# Pure_Seq_SMD_V2_2.net
KiCad netlist of a schematic drawn in EAGLE
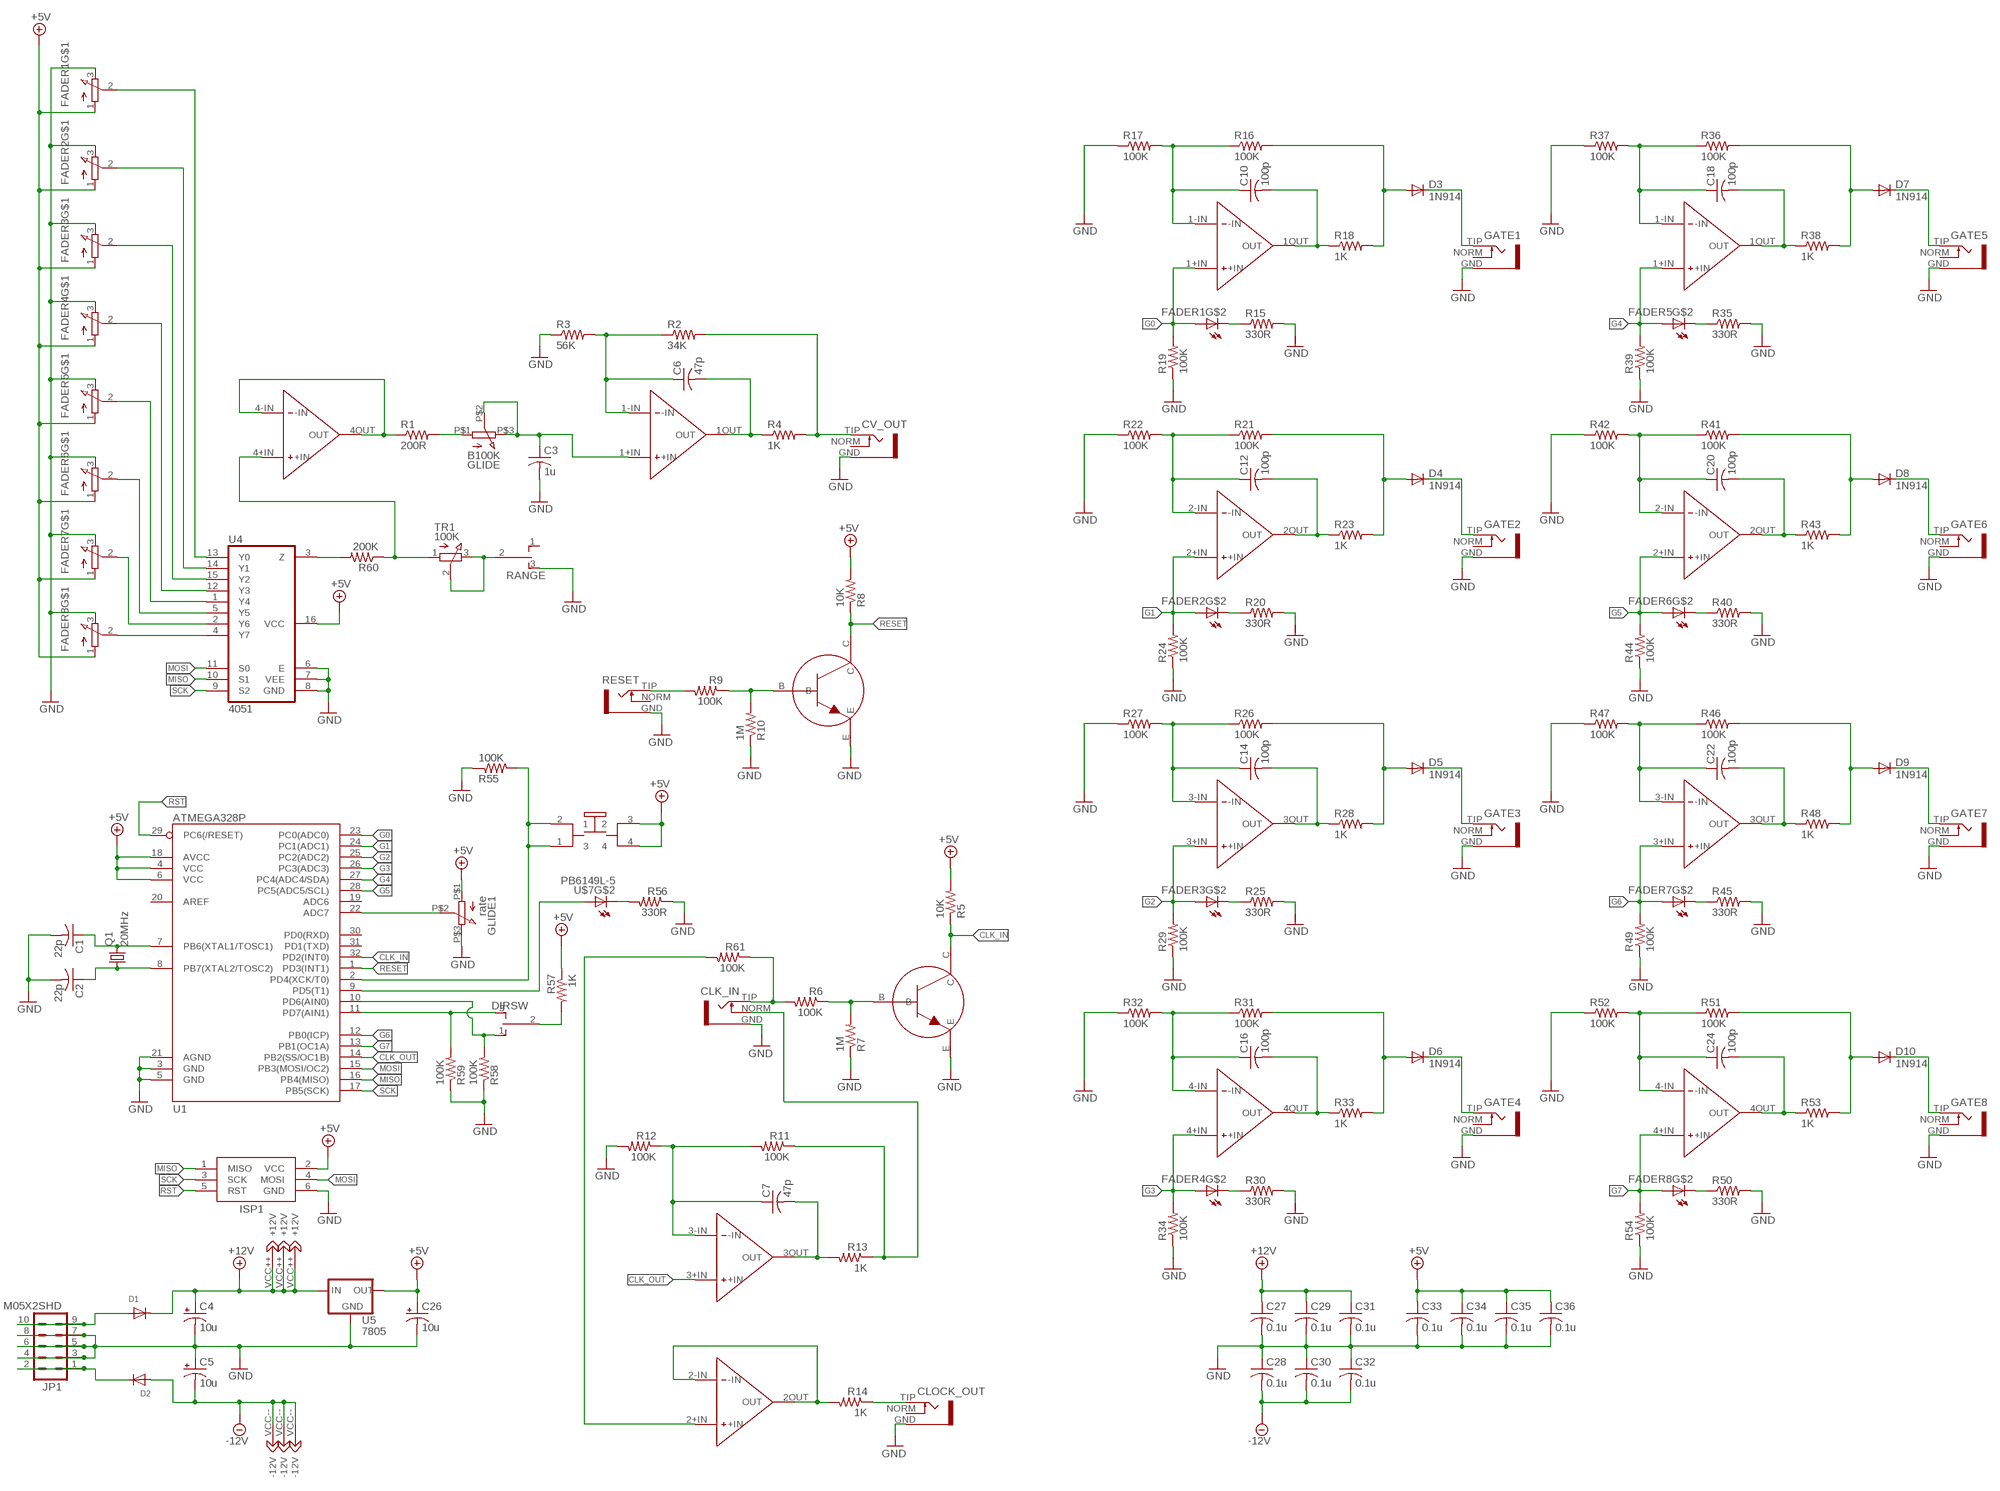
[diagram p0: schematic, sheet 1]

(export (version "E")
  (design (tool "Eeschema 10.0.6"))
  (components
    (comp (ref "C1")
      (value "22p")
      (footprint "eagle-import:C0805K")
      (libsource (lib "eagle-import") (part "C-USC0805K"))
    )
    (comp (ref "C2")
      (value "22p")
      (footprint "eagle-import:C0805K")
      (libsource (lib "eagle-import") (part "C-USC0805K"))
    )
    (comp (ref "C3")
      (value "1u")
      (footprint "eagle-import:C0805K")
      (libsource (lib "eagle-import") (part "C-USC0805K"))
    )
    (comp (ref "C4")
      (value "10u")
      (footprint "eagle-import:153CLV-0505")
      (libsource (lib "eagle-import") (part "CPOL-US153CLV-0505"))
    )
    (comp (ref "C5")
      (value "10u")
      (footprint "eagle-import:153CLV-0505")
      (libsource (lib "eagle-import") (part "CPOL-US153CLV-0505"))
    )
    (comp (ref "C6")
      (value "47p")
      (footprint "eagle-import:C0805K")
      (libsource (lib "eagle-import") (part "C-USC0805K"))
    )
    (comp (ref "C7")
      (value "47p")
      (footprint "eagle-import:C0805K")
      (libsource (lib "eagle-import") (part "C-USC0805K"))
    )
    (comp (ref "C10")
      (value "100p")
      (footprint "eagle-import:C0805K")
      (libsource (lib "eagle-import") (part "C-USC0805K"))
    )
    (comp (ref "C12")
      (value "100p")
      (footprint "eagle-import:C0805K")
      (libsource (lib "eagle-import") (part "C-USC0805K"))
    )
    (comp (ref "C14")
      (value "100p")
      (footprint "eagle-import:C0805K")
      (libsource (lib "eagle-import") (part "C-USC0805K"))
    )
    (comp (ref "C16")
      (value "100p")
      (footprint "eagle-import:C0805K")
      (libsource (lib "eagle-import") (part "C-USC0805K"))
    )
    (comp (ref "C18")
      (value "100p")
      (footprint "eagle-import:C0805K")
      (libsource (lib "eagle-import") (part "C-USC0805K"))
    )
    (comp (ref "C20")
      (value "100p")
      (footprint "eagle-import:C0805K")
      (libsource (lib "eagle-import") (part "C-USC0805K"))
    )
    (comp (ref "C22")
      (value "100p")
      (footprint "eagle-import:C0805K")
      (libsource (lib "eagle-import") (part "C-USC0805K"))
    )
    (comp (ref "C24")
      (value "100p")
      (footprint "eagle-import:C0805K")
      (libsource (lib "eagle-import") (part "C-USC0805K"))
    )
    (comp (ref "C26")
      (value "10u")
      (footprint "eagle-import:153CLV-0505")
      (libsource (lib "eagle-import") (part "CPOL-US153CLV-0505"))
    )
    (comp (ref "C27")
      (value "0.1u")
      (footprint "eagle-import:C0805K")
      (libsource (lib "eagle-import") (part "C-USC0805K"))
    )
    (comp (ref "C28")
      (value "0.1u")
      (footprint "eagle-import:C0805K")
      (libsource (lib "eagle-import") (part "C-USC0805K"))
    )
    (comp (ref "C29")
      (value "0.1u")
      (footprint "eagle-import:C0805K")
      (libsource (lib "eagle-import") (part "C-USC0805K"))
    )
    (comp (ref "C30")
      (value "0.1u")
      (footprint "eagle-import:C0805K")
      (libsource (lib "eagle-import") (part "C-USC0805K"))
    )
    (comp (ref "C31")
      (value "0.1u")
      (footprint "eagle-import:C0805K")
      (libsource (lib "eagle-import") (part "C-USC0805K"))
    )
    (comp (ref "C32")
      (value "0.1u")
      (footprint "eagle-import:C0805K")
      (libsource (lib "eagle-import") (part "C-USC0805K"))
    )
    (comp (ref "C33")
      (value "0.1u")
      (footprint "eagle-import:C0805K")
      (libsource (lib "eagle-import") (part "C-USC0805K"))
    )
    (comp (ref "C34")
      (value "0.1u")
      (footprint "eagle-import:C0805K")
      (libsource (lib "eagle-import") (part "C-USC0805K"))
    )
    (comp (ref "C35")
      (value "0.1u")
      (footprint "eagle-import:C0805K")
      (libsource (lib "eagle-import") (part "C-USC0805K"))
    )
    (comp (ref "C36")
      (value "0.1u")
      (footprint "eagle-import:C0805K")
      (libsource (lib "eagle-import") (part "C-USC0805K"))
    )
    (comp (ref "CLK_IN")
      (value "S_JACK")
      (footprint "eagle-import:S_JACK")
      (libsource (lib "eagle-import") (part "S_JACK"))
    )
    (comp (ref "CLOCK_OUT")
      (value "S_JACK")
      (footprint "eagle-import:S_JACK")
      (libsource (lib "eagle-import") (part "S_JACK"))
    )
    (comp (ref "CV_OUT")
      (value "S_JACK")
      (footprint "eagle-import:S_JACK")
      (libsource (lib "eagle-import") (part "S_JACK"))
    )
    (comp (ref "D1")
      (value "DIODESMA")
      (footprint "eagle-import:SMADIODE")
      (libsource (lib "eagle-import") (part "adafruit_DIODESMA"))
    )
    (comp (ref "D2")
      (value "DIODESMA")
      (footprint "eagle-import:SMADIODE")
      (libsource (lib "eagle-import") (part "adafruit_DIODESMA"))
    )
    (comp (ref "D3")
      (value "1N914")
      (footprint "eagle-import:SOD-323")
      (libsource (lib "eagle-import") (part "DIODESOD"))
    )
    (comp (ref "D4")
      (value "1N914")
      (footprint "eagle-import:SOD-323")
      (libsource (lib "eagle-import") (part "DIODESOD"))
    )
    (comp (ref "D5")
      (value "1N914")
      (footprint "eagle-import:SOD-323")
      (libsource (lib "eagle-import") (part "DIODESOD"))
    )
    (comp (ref "D6")
      (value "1N914")
      (footprint "eagle-import:SOD-323")
      (libsource (lib "eagle-import") (part "DIODESOD"))
    )
    (comp (ref "D7")
      (value "1N914")
      (footprint "eagle-import:SOD-323")
      (libsource (lib "eagle-import") (part "DIODESOD"))
    )
    (comp (ref "D8")
      (value "1N914")
      (footprint "eagle-import:SOD-323")
      (libsource (lib "eagle-import") (part "DIODESOD"))
    )
    (comp (ref "D9")
      (value "1N914")
      (footprint "eagle-import:SOD-323")
      (libsource (lib "eagle-import") (part "DIODESOD"))
    )
    (comp (ref "D10")
      (value "1N914")
      (footprint "eagle-import:SOD-323")
      (libsource (lib "eagle-import") (part "DIODESOD"))
    )
    (comp (ref "DIRSW")
      (value "TOGGLE_ON_OFF_ON")
      (footprint "eagle-import:TOGGLE_ON_OFF_ON")
      (libsource (lib "eagle-import") (part "TOGGLE_ON_OFF_ON"))
    )
    (comp (ref "FADER1")
      (value "LED_FADER")
      (footprint "eagle-import:LED_FADER")
      (libsource (lib "eagle-import") (part "LED_FADER"))
    )
    (comp (ref "FADER2")
      (value "LED_FADER")
      (footprint "eagle-import:LED_FADER")
      (libsource (lib "eagle-import") (part "LED_FADER"))
    )
    (comp (ref "FADER3")
      (value "LED_FADER")
      (footprint "eagle-import:LED_FADER")
      (libsource (lib "eagle-import") (part "LED_FADER"))
    )
    (comp (ref "FADER4")
      (value "LED_FADER")
      (footprint "eagle-import:LED_FADER")
      (libsource (lib "eagle-import") (part "LED_FADER"))
    )
    (comp (ref "FADER5")
      (value "LED_FADER")
      (footprint "eagle-import:LED_FADER")
      (libsource (lib "eagle-import") (part "LED_FADER"))
    )
    (comp (ref "FADER6")
      (value "LED_FADER")
      (footprint "eagle-import:LED_FADER")
      (libsource (lib "eagle-import") (part "LED_FADER"))
    )
    (comp (ref "FADER7")
      (value "LED_FADER")
      (footprint "eagle-import:LED_FADER")
      (libsource (lib "eagle-import") (part "LED_FADER"))
    )
    (comp (ref "FADER8")
      (value "LED_FADER")
      (footprint "eagle-import:LED_FADER")
      (libsource (lib "eagle-import") (part "LED_FADER"))
    )
    (comp (ref "GATE1")
      (value "S_JACK")
      (footprint "eagle-import:S_JACK")
      (libsource (lib "eagle-import") (part "S_JACK"))
    )
    (comp (ref "GATE2")
      (value "S_JACK")
      (footprint "eagle-import:S_JACK")
      (libsource (lib "eagle-import") (part "S_JACK"))
    )
    (comp (ref "GATE3")
      (value "S_JACK")
      (footprint "eagle-import:S_JACK")
      (libsource (lib "eagle-import") (part "S_JACK"))
    )
    (comp (ref "GATE4")
      (value "S_JACK")
      (footprint "eagle-import:S_JACK")
      (libsource (lib "eagle-import") (part "S_JACK"))
    )
    (comp (ref "GATE5")
      (value "S_JACK")
      (footprint "eagle-import:S_JACK")
      (libsource (lib "eagle-import") (part "S_JACK"))
    )
    (comp (ref "GATE6")
      (value "S_JACK")
      (footprint "eagle-import:S_JACK")
      (libsource (lib "eagle-import") (part "S_JACK"))
    )
    (comp (ref "GATE7")
      (value "S_JACK")
      (footprint "eagle-import:S_JACK")
      (libsource (lib "eagle-import") (part "S_JACK"))
    )
    (comp (ref "GATE8")
      (value "S_JACK")
      (footprint "eagle-import:S_JACK")
      (libsource (lib "eagle-import") (part "S_JACK"))
    )
    (comp (ref "GLIDE")
      (value "B100K")
      (footprint "eagle-import:Q-POT")
      (libsource (lib "eagle-import") (part "Q-POT"))
    )
    (comp (ref "GLIDE1")
      (value "rate")
      (footprint "eagle-import:Q-POT")
      (libsource (lib "eagle-import") (part "Q-POT"))
    )
    (comp (ref "ISP1")
      (value "AVRISP-6")
      (footprint "eagle-import:AVRISP")
      (libsource (lib "eagle-import") (part "AVRISP-6"))
    )
    (comp (ref "JP1")
      (value "M05X2SHD")
      (footprint "eagle-import:2X5-SHROUDED")
      (libsource (lib "eagle-import") (part "M05X2SHD"))
    )
    (comp (ref "Q1")
      (value "20MHz")
      (footprint "eagle-import:HC49UP")
      (libsource (lib "eagle-import") (part "CRYSTALHC49UP"))
    )
    (comp (ref "R1")
      (value "200R")
      (footprint "eagle-import:R0805")
      (libsource (lib "eagle-import") (part "R-US_R0805"))
    )
    (comp (ref "R2")
      (value "34K")
      (footprint "eagle-import:R0805")
      (libsource (lib "eagle-import") (part "R-US_R0805"))
    )
    (comp (ref "R3")
      (value "56K")
      (footprint "eagle-import:R0805")
      (libsource (lib "eagle-import") (part "R-US_R0805"))
    )
    (comp (ref "R4")
      (value "1K")
      (footprint "eagle-import:R0805")
      (libsource (lib "eagle-import") (part "R-US_R0805"))
    )
    (comp (ref "R5")
      (value "10K")
      (footprint "eagle-import:R0805")
      (libsource (lib "eagle-import") (part "R-US_R0805"))
    )
    (comp (ref "R6")
      (value "100K")
      (footprint "eagle-import:R0805")
      (libsource (lib "eagle-import") (part "R-US_R0805"))
    )
    (comp (ref "R7")
      (value "1M")
      (footprint "eagle-import:R0805")
      (libsource (lib "eagle-import") (part "R-US_R0805"))
    )
    (comp (ref "R8")
      (value "10K")
      (footprint "eagle-import:R0805")
      (libsource (lib "eagle-import") (part "R-US_R0805"))
    )
    (comp (ref "R9")
      (value "100K")
      (footprint "eagle-import:R0805")
      (libsource (lib "eagle-import") (part "R-US_R0805"))
    )
    (comp (ref "R10")
      (value "1M")
      (footprint "eagle-import:R0805")
      (libsource (lib "eagle-import") (part "R-US_R0805"))
    )
    (comp (ref "R11")
      (value "100K")
      (footprint "eagle-import:R0805")
      (libsource (lib "eagle-import") (part "R-US_R0805"))
    )
    (comp (ref "R12")
      (value "100K")
      (footprint "eagle-import:R0805")
      (libsource (lib "eagle-import") (part "R-US_R0805"))
    )
    (comp (ref "R13")
      (value "1K")
      (footprint "eagle-import:R0805")
      (libsource (lib "eagle-import") (part "R-US_R0805"))
    )
    (comp (ref "R14")
      (value "1K")
      (footprint "eagle-import:R0805")
      (libsource (lib "eagle-import") (part "R-US_R0805"))
    )
    (comp (ref "R15")
      (value "330R")
      (footprint "eagle-import:R0805")
      (libsource (lib "eagle-import") (part "R-US_R0805"))
    )
    (comp (ref "R16")
      (value "100K")
      (footprint "eagle-import:R0805")
      (libsource (lib "eagle-import") (part "R-US_R0805"))
    )
    (comp (ref "R17")
      (value "100K")
      (footprint "eagle-import:R0805")
      (libsource (lib "eagle-import") (part "R-US_R0805"))
    )
    (comp (ref "R18")
      (value "1K")
      (footprint "eagle-import:R0805")
      (libsource (lib "eagle-import") (part "R-US_R0805"))
    )
    (comp (ref "R19")
      (value "100K")
      (footprint "eagle-import:R0805")
      (libsource (lib "eagle-import") (part "R-US_R0805"))
    )
    (comp (ref "R20")
      (value "330R")
      (footprint "eagle-import:R0805")
      (libsource (lib "eagle-import") (part "R-US_R0805"))
    )
    (comp (ref "R21")
      (value "100K")
      (footprint "eagle-import:R0805")
      (libsource (lib "eagle-import") (part "R-US_R0805"))
    )
    (comp (ref "R22")
      (value "100K")
      (footprint "eagle-import:R0805")
      (libsource (lib "eagle-import") (part "R-US_R0805"))
    )
    (comp (ref "R23")
      (value "1K")
      (footprint "eagle-import:R0805")
      (libsource (lib "eagle-import") (part "R-US_R0805"))
    )
    (comp (ref "R24")
      (value "100K")
      (footprint "eagle-import:R0805")
      (libsource (lib "eagle-import") (part "R-US_R0805"))
    )
    (comp (ref "R25")
      (value "330R")
      (footprint "eagle-import:R0805")
      (libsource (lib "eagle-import") (part "R-US_R0805"))
    )
    (comp (ref "R26")
      (value "100K")
      (footprint "eagle-import:R0805")
      (libsource (lib "eagle-import") (part "R-US_R0805"))
    )
    (comp (ref "R27")
      (value "100K")
      (footprint "eagle-import:R0805")
      (libsource (lib "eagle-import") (part "R-US_R0805"))
    )
    (comp (ref "R28")
      (value "1K")
      (footprint "eagle-import:R0805")
      (libsource (lib "eagle-import") (part "R-US_R0805"))
    )
    (comp (ref "R29")
      (value "100K")
      (footprint "eagle-import:R0805")
      (libsource (lib "eagle-import") (part "R-US_R0805"))
    )
    (comp (ref "R30")
      (value "330R")
      (footprint "eagle-import:R0805")
      (libsource (lib "eagle-import") (part "R-US_R0805"))
    )
    (comp (ref "R31")
      (value "100K")
      (footprint "eagle-import:R0805")
      (libsource (lib "eagle-import") (part "R-US_R0805"))
    )
    (comp (ref "R32")
      (value "100K")
      (footprint "eagle-import:R0805")
      (libsource (lib "eagle-import") (part "R-US_R0805"))
    )
    (comp (ref "R33")
      (value "1K")
      (footprint "eagle-import:R0805")
      (libsource (lib "eagle-import") (part "R-US_R0805"))
    )
    (comp (ref "R34")
      (value "100K")
      (footprint "eagle-import:R0805")
      (libsource (lib "eagle-import") (part "R-US_R0805"))
    )
    (comp (ref "R35")
      (value "330R")
      (footprint "eagle-import:R0805")
      (libsource (lib "eagle-import") (part "R-US_R0805"))
    )
    (comp (ref "R36")
      (value "100K")
      (footprint "eagle-import:R0805")
      (libsource (lib "eagle-import") (part "R-US_R0805"))
    )
    (comp (ref "R37")
      (value "100K")
      (footprint "eagle-import:R0805")
      (libsource (lib "eagle-import") (part "R-US_R0805"))
    )
    (comp (ref "R38")
      (value "1K")
      (footprint "eagle-import:R0805")
      (libsource (lib "eagle-import") (part "R-US_R0805"))
    )
    (comp (ref "R39")
      (value "100K")
      (footprint "eagle-import:R0805")
      (libsource (lib "eagle-import") (part "R-US_R0805"))
    )
    (comp (ref "R40")
      (value "330R")
      (footprint "eagle-import:R0805")
      (libsource (lib "eagle-import") (part "R-US_R0805"))
    )
    (comp (ref "R41")
      (value "100K")
      (footprint "eagle-import:R0805")
      (libsource (lib "eagle-import") (part "R-US_R0805"))
    )
    (comp (ref "R42")
      (value "100K")
      (footprint "eagle-import:R0805")
      (libsource (lib "eagle-import") (part "R-US_R0805"))
    )
    (comp (ref "R43")
      (value "1K")
      (footprint "eagle-import:R0805")
      (libsource (lib "eagle-import") (part "R-US_R0805"))
    )
    (comp (ref "R44")
      (value "100K")
      (footprint "eagle-import:R0805")
      (libsource (lib "eagle-import") (part "R-US_R0805"))
    )
    (comp (ref "R45")
      (value "330R")
      (footprint "eagle-import:R0805")
      (libsource (lib "eagle-import") (part "R-US_R0805"))
    )
    (comp (ref "R46")
      (value "100K")
      (footprint "eagle-import:R0805")
      (libsource (lib "eagle-import") (part "R-US_R0805"))
    )
    (comp (ref "R47")
      (value "100K")
      (footprint "eagle-import:R0805")
      (libsource (lib "eagle-import") (part "R-US_R0805"))
    )
    (comp (ref "R48")
      (value "1K")
      (footprint "eagle-import:R0805")
      (libsource (lib "eagle-import") (part "R-US_R0805"))
    )
    (comp (ref "R49")
      (value "100K")
      (footprint "eagle-import:R0805")
      (libsource (lib "eagle-import") (part "R-US_R0805"))
    )
    (comp (ref "R50")
      (value "330R")
      (footprint "eagle-import:R0805")
      (libsource (lib "eagle-import") (part "R-US_R0805"))
    )
    (comp (ref "R51")
      (value "100K")
      (footprint "eagle-import:R0805")
      (libsource (lib "eagle-import") (part "R-US_R0805"))
    )
    (comp (ref "R52")
      (value "100K")
      (footprint "eagle-import:R0805")
      (libsource (lib "eagle-import") (part "R-US_R0805"))
    )
    (comp (ref "R53")
      (value "1K")
      (footprint "eagle-import:R0805")
      (libsource (lib "eagle-import") (part "R-US_R0805"))
    )
    (comp (ref "R54")
      (value "100K")
      (footprint "eagle-import:R0805")
      (libsource (lib "eagle-import") (part "R-US_R0805"))
    )
    (comp (ref "R55")
      (value "100K")
      (footprint "eagle-import:R0805")
      (libsource (lib "eagle-import") (part "R-US_R0805"))
    )
    (comp (ref "R56")
      (value "330R")
      (footprint "eagle-import:R0805")
      (libsource (lib "eagle-import") (part "R-US_R0805"))
    )
    (comp (ref "R57")
      (value "1K")
      (footprint "eagle-import:R0805")
      (libsource (lib "eagle-import") (part "R-US_R0805"))
    )
    (comp (ref "R58")
      (value "100K")
      (footprint "eagle-import:R0805")
      (libsource (lib "eagle-import") (part "R-US_R0805"))
    )
    (comp (ref "R59")
      (value "100K")
      (footprint "eagle-import:R0805")
      (libsource (lib "eagle-import") (part "R-US_R0805"))
    )
    (comp (ref "R60")
      (value "200K")
      (footprint "eagle-import:R0805")
      (libsource (lib "eagle-import") (part "R-US_R0805"))
    )
    (comp (ref "R61")
      (value "100K")
      (footprint "eagle-import:R0805")
      (libsource (lib "eagle-import") (part "R-US_R0805"))
    )
    (comp (ref "RANGE")
      (value "TOGGLE_ON_OFF_ON")
      (footprint "eagle-import:TOGGLE_ON_OFF_ON")
      (libsource (lib "eagle-import") (part "TOGGLE_ON_OFF_ON"))
    )
    (comp (ref "RESET")
      (value "S_JACK")
      (footprint "eagle-import:S_JACK")
      (libsource (lib "eagle-import") (part "S_JACK"))
    )
    (comp (ref "T1")
      (value "2N3904")
      (footprint "eagle-import:TRANSISTOR_SINGLE_N-TYPE")
      (libsource (lib "eagle-import") (part "TRANSISTOR_MMBT3904"))
    )
    (comp (ref "T2")
      (value "2N3904")
      (footprint "eagle-import:TRANSISTOR_SINGLE_N-TYPE")
      (libsource (lib "eagle-import") (part "TRANSISTOR_MMBT3904"))
    )
    (comp (ref "TR1")
      (value "100K")
      (footprint "eagle-import:TRIMMER_TH3")
      (libsource (lib "eagle-import") (part "TRIMMER_TH3"))
    )
    (comp (ref "U$7")
      (value "PB6149L-5")
      (footprint "eagle-import:PB6149L")
      (libsource (lib "eagle-import") (part "PB6149L-5"))
    )
    (comp (ref "U1")
      (value "ATMEGA328P")
      (footprint "eagle-import:TQFP32-08")
      (libsource (lib "eagle-import") (part "ATMEGA328_SMT"))
    )
    (comp (ref "U2")
      (value "QUAD_OPAMP")
      (footprint "eagle-import:QUAD_OPAMP")
      (libsource (lib "eagle-import") (part "QUAD_OPAMP"))
    )
    (comp (ref "U3")
      (value "QUAD_OPAMP")
      (footprint "eagle-import:QUAD_OPAMP")
      (libsource (lib "eagle-import") (part "QUAD_OPAMP"))
    )
    (comp (ref "U4")
      (value "4051")
      (footprint "eagle-import:N2222_ARRAY")
      (libsource (lib "eagle-import") (part "MUX!"))
    )
    (comp (ref "U5")
      (value "7805")
      (footprint "eagle-import:V-REG")
      (libsource (lib "eagle-import") (part "V-REG"))
    )
    (comp (ref "U6")
      (value "QUAD_OPAMP")
      (footprint "eagle-import:QUAD_OPAMP")
      (libsource (lib "eagle-import") (part "QUAD_OPAMP"))
    )
  )
  (nets
    (net (code "1") (name "+5V") (class "Default")
      (node (ref "C26") (pin "+") (pinfunction "+_+") (pintype "passive"))
      (node (ref "C33") (pin "1") (pinfunction "1_1") (pintype "passive"))
      (node (ref "C34") (pin "1") (pinfunction "1_1") (pintype "passive"))
      (node (ref "C35") (pin "1") (pinfunction "1_1") (pintype "passive"))
      (node (ref "C36") (pin "1") (pinfunction "1_1") (pintype "passive"))
      (node (ref "FADER1") (pin "1") (pinfunction "1_1") (pintype "passive"))
      (node (ref "FADER2") (pin "1") (pinfunction "1_1") (pintype "passive"))
      (node (ref "FADER3") (pin "1") (pinfunction "1_1") (pintype "passive"))
      (node (ref "FADER4") (pin "1") (pinfunction "1_1") (pintype "passive"))
      (node (ref "FADER5") (pin "1") (pinfunction "1_1") (pintype "passive"))
      (node (ref "FADER6") (pin "1") (pinfunction "1_1") (pintype "passive"))
      (node (ref "FADER7") (pin "1") (pinfunction "1_1") (pintype "passive"))
      (node (ref "FADER8") (pin "1") (pinfunction "1_1") (pintype "passive"))
      (node (ref "GLIDE1") (pin "P$1") (pinfunction "1_P$1") (pintype "passive"))
      (node (ref "ISP1") (pin "2") (pinfunction "VCC_2") (pintype "power_in"))
      (node (ref "R5") (pin "2") (pinfunction "2_2") (pintype "passive"))
      (node (ref "R57") (pin "1") (pinfunction "1_1") (pintype "passive"))
      (node (ref "R8") (pin "2") (pinfunction "2_2") (pintype "passive"))
      (node (ref "U$7") (pin "3") (pinfunction "2_3") (pintype "bidirectional"))
      (node (ref "U$7") (pin "4") (pinfunction "4_4") (pintype "bidirectional"))
      (node (ref "U1") (pin "18") (pinfunction "AVCC_18") (pintype "bidirectional"))
      (node (ref "U1") (pin "4") (pinfunction "VCC_4") (pintype "bidirectional"))
      (node (ref "U1") (pin "6") (pinfunction "VCC_6") (pintype "bidirectional"))
      (node (ref "U4") (pin "16") (pinfunction "VCC_16") (pintype "input"))
      (node (ref "U5") (pin "3") (pinfunction "OUT_3") (pintype "passive"))
    )
    (net (code "2") (name "+12V") (class "Default")
      (node (ref "C27") (pin "1") (pinfunction "1_1") (pintype "passive"))
      (node (ref "C29") (pin "1") (pinfunction "1_1") (pintype "passive"))
      (node (ref "C31") (pin "1") (pinfunction "1_1") (pintype "passive"))
      (node (ref "C4") (pin "+") (pinfunction "+_+") (pintype "passive"))
      (node (ref "D1") (pin "C") (pinfunction "C_C") (pintype "passive"))
      (node (ref "U2") (pin "VCC++") (pinfunction "+12V_VCC++") (pintype "bidirectional"))
      (node (ref "U3") (pin "VCC++") (pinfunction "+12V_VCC++") (pintype "bidirectional"))
      (node (ref "U5") (pin "1") (pinfunction "IN_1") (pintype "input"))
      (node (ref "U6") (pin "VCC++") (pinfunction "+12V_VCC++") (pintype "bidirectional"))
    )
    (net (code "3") (name "-12V") (class "Default")
      (node (ref "C28") (pin "2") (pinfunction "2_2") (pintype "passive"))
      (node (ref "C30") (pin "2") (pinfunction "2_2") (pintype "passive"))
      (node (ref "C32") (pin "2") (pinfunction "2_2") (pintype "passive"))
      (node (ref "C5") (pin "-") (pinfunction "-_-") (pintype "passive"))
      (node (ref "D2") (pin "A") (pinfunction "A_A") (pintype "passive"))
      (node (ref "U2") (pin "VCC--") (pinfunction "-12V_VCC--") (pintype "bidirectional"))
      (node (ref "U3") (pin "VCC--") (pinfunction "-12V_VCC--") (pintype "bidirectional"))
      (node (ref "U6") (pin "VCC--") (pinfunction "-12V_VCC--") (pintype "bidirectional"))
    )
    (net (code "4") (name "CLK_IN") (class "Default")
      (node (ref "R5") (pin "1") (pinfunction "1_1") (pintype "passive"))
      (node (ref "T1") (pin "C") (pinfunction "C_C") (pintype "bidirectional"))
      (node (ref "U1") (pin "32") (pinfunction "PD2(INT0)_32") (pintype "bidirectional"))
    )
    (net (code "5") (name "CLK_OUT") (class "Default")
      (node (ref "U1") (pin "14") (pinfunction "PB2(SS/OC1B)_14") (pintype "bidirectional"))
      (node (ref "U6") (pin "3+IN") (pinfunction "+IN_3+IN") (pintype "bidirectional"))
    )
    (net (code "6") (name "G0") (class "Default")
      (node (ref "FADER1") (pin "A") (pinfunction "A_A") (pintype "passive"))
      (node (ref "R19") (pin "2") (pinfunction "2_2") (pintype "passive"))
      (node (ref "U1") (pin "23") (pinfunction "PC0(ADC0)_23") (pintype "bidirectional"))
      (node (ref "U2") (pin "1+IN") (pinfunction "+IN_1+IN") (pintype "bidirectional"))
    )
    (net (code "7") (name "G1") (class "Default")
      (node (ref "FADER2") (pin "A") (pinfunction "A_A") (pintype "passive"))
      (node (ref "R24") (pin "2") (pinfunction "2_2") (pintype "passive"))
      (node (ref "U1") (pin "24") (pinfunction "PC1(ADC1)_24") (pintype "bidirectional"))
      (node (ref "U2") (pin "2+IN") (pinfunction "+IN_2+IN") (pintype "bidirectional"))
    )
    (net (code "8") (name "G2") (class "Default")
      (node (ref "FADER3") (pin "A") (pinfunction "A_A") (pintype "passive"))
      (node (ref "R29") (pin "2") (pinfunction "2_2") (pintype "passive"))
      (node (ref "U1") (pin "25") (pinfunction "PC2(ADC2)_25") (pintype "bidirectional"))
      (node (ref "U2") (pin "3+IN") (pinfunction "+IN_3+IN") (pintype "bidirectional"))
    )
    (net (code "9") (name "G3") (class "Default")
      (node (ref "FADER4") (pin "A") (pinfunction "A_A") (pintype "passive"))
      (node (ref "R34") (pin "2") (pinfunction "2_2") (pintype "passive"))
      (node (ref "U1") (pin "26") (pinfunction "PC3(ADC3)_26") (pintype "bidirectional"))
      (node (ref "U2") (pin "4+IN") (pinfunction "+IN_4+IN") (pintype "bidirectional"))
    )
    (net (code "10") (name "G4") (class "Default")
      (node (ref "FADER5") (pin "A") (pinfunction "A_A") (pintype "passive"))
      (node (ref "R39") (pin "2") (pinfunction "2_2") (pintype "passive"))
      (node (ref "U1") (pin "27") (pinfunction "PC4(ADC4/SDA)_27") (pintype "bidirectional"))
      (node (ref "U3") (pin "1+IN") (pinfunction "+IN_1+IN") (pintype "bidirectional"))
    )
    (net (code "11") (name "G5") (class "Default")
      (node (ref "FADER6") (pin "A") (pinfunction "A_A") (pintype "passive"))
      (node (ref "R44") (pin "2") (pinfunction "2_2") (pintype "passive"))
      (node (ref "U1") (pin "28") (pinfunction "PC5(ADC5/SCL)_28") (pintype "bidirectional"))
      (node (ref "U3") (pin "2+IN") (pinfunction "+IN_2+IN") (pintype "bidirectional"))
    )
    (net (code "12") (name "G6") (class "Default")
      (node (ref "FADER7") (pin "A") (pinfunction "A_A") (pintype "passive"))
      (node (ref "R49") (pin "2") (pinfunction "2_2") (pintype "passive"))
      (node (ref "U1") (pin "12") (pinfunction "PB0(ICP)_12") (pintype "bidirectional"))
      (node (ref "U3") (pin "3+IN") (pinfunction "+IN_3+IN") (pintype "bidirectional"))
    )
    (net (code "13") (name "G7") (class "Default")
      (node (ref "FADER8") (pin "A") (pinfunction "A_A") (pintype "passive"))
      (node (ref "R54") (pin "2") (pinfunction "2_2") (pintype "passive"))
      (node (ref "U1") (pin "13") (pinfunction "PB1(OC1A)_13") (pintype "bidirectional"))
      (node (ref "U3") (pin "4+IN") (pinfunction "+IN_4+IN") (pintype "bidirectional"))
    )
    (net (code "14") (name "GND") (class "Default")
      (node (ref "C1") (pin "2") (pinfunction "2_2") (pintype "passive"))
      (node (ref "C2") (pin "2") (pinfunction "2_2") (pintype "passive"))
      (node (ref "C26") (pin "-") (pinfunction "-_-") (pintype "passive"))
      (node (ref "C27") (pin "2") (pinfunction "2_2") (pintype "passive"))
      (node (ref "C28") (pin "1") (pinfunction "1_1") (pintype "passive"))
      (node (ref "C29") (pin "2") (pinfunction "2_2") (pintype "passive"))
      (node (ref "C3") (pin "2") (pinfunction "2_2") (pintype "passive"))
      (node (ref "C30") (pin "1") (pinfunction "1_1") (pintype "passive"))
      (node (ref "C31") (pin "2") (pinfunction "2_2") (pintype "passive"))
      (node (ref "C32") (pin "1") (pinfunction "1_1") (pintype "passive"))
      (node (ref "C33") (pin "2") (pinfunction "2_2") (pintype "passive"))
      (node (ref "C34") (pin "2") (pinfunction "2_2") (pintype "passive"))
      (node (ref "C35") (pin "2") (pinfunction "2_2") (pintype "passive"))
      (node (ref "C36") (pin "2") (pinfunction "2_2") (pintype "passive"))
      (node (ref "C4") (pin "-") (pinfunction "-_-") (pintype "passive"))
      (node (ref "C5") (pin "+") (pinfunction "+_+") (pintype "passive"))
      (node (ref "CLK_IN") (pin "GND") (pinfunction "GND_GND") (pintype "passive"))
      (node (ref "CLOCK_OUT") (pin "GND") (pinfunction "GND_GND") (pintype "passive"))
      (node (ref "CV_OUT") (pin "GND") (pinfunction "GND_GND") (pintype "passive"))
      (node (ref "FADER1") (pin "3") (pinfunction "3_3") (pintype "passive"))
      (node (ref "FADER2") (pin "3") (pinfunction "3_3") (pintype "passive"))
      (node (ref "FADER3") (pin "3") (pinfunction "3_3") (pintype "passive"))
      (node (ref "FADER4") (pin "3") (pinfunction "3_3") (pintype "passive"))
      (node (ref "FADER5") (pin "3") (pinfunction "3_3") (pintype "passive"))
      (node (ref "FADER6") (pin "3") (pinfunction "3_3") (pintype "passive"))
      (node (ref "FADER7") (pin "3") (pinfunction "3_3") (pintype "passive"))
      (node (ref "FADER8") (pin "3") (pinfunction "3_3") (pintype "passive"))
      (node (ref "GATE1") (pin "GND") (pinfunction "GND_GND") (pintype "passive"))
      (node (ref "GATE2") (pin "GND") (pinfunction "GND_GND") (pintype "passive"))
      (node (ref "GATE3") (pin "GND") (pinfunction "GND_GND") (pintype "passive"))
      (node (ref "GATE4") (pin "GND") (pinfunction "GND_GND") (pintype "passive"))
      (node (ref "GATE5") (pin "GND") (pinfunction "GND_GND") (pintype "passive"))
      (node (ref "GATE6") (pin "GND") (pinfunction "GND_GND") (pintype "passive"))
      (node (ref "GATE7") (pin "GND") (pinfunction "GND_GND") (pintype "passive"))
      (node (ref "GATE8") (pin "GND") (pinfunction "GND_GND") (pintype "passive"))
      (node (ref "GLIDE1") (pin "P$3") (pinfunction "3_P$3") (pintype "passive"))
      (node (ref "ISP1") (pin "6") (pinfunction "GND_6") (pintype "power_in"))
      (node (ref "JP1") (pin "3") (pinfunction "3_3") (pintype "passive"))
      (node (ref "JP1") (pin "4") (pinfunction "4_4") (pintype "passive"))
      (node (ref "JP1") (pin "5") (pinfunction "5_5") (pintype "passive"))
      (node (ref "JP1") (pin "6") (pinfunction "6_6") (pintype "passive"))
      (node (ref "JP1") (pin "7") (pinfunction "7_7") (pintype "passive"))
      (node (ref "JP1") (pin "8") (pinfunction "8_8") (pintype "passive"))
      (node (ref "R10") (pin "1") (pinfunction "1_1") (pintype "passive"))
      (node (ref "R12") (pin "2") (pinfunction "2_2") (pintype "passive"))
      (node (ref "R15") (pin "2") (pinfunction "2_2") (pintype "passive"))
      (node (ref "R17") (pin "1") (pinfunction "1_1") (pintype "passive"))
      (node (ref "R19") (pin "1") (pinfunction "1_1") (pintype "passive"))
      (node (ref "R20") (pin "2") (pinfunction "2_2") (pintype "passive"))
      (node (ref "R22") (pin "1") (pinfunction "1_1") (pintype "passive"))
      (node (ref "R24") (pin "1") (pinfunction "1_1") (pintype "passive"))
      (node (ref "R25") (pin "2") (pinfunction "2_2") (pintype "passive"))
      (node (ref "R27") (pin "1") (pinfunction "1_1") (pintype "passive"))
      (node (ref "R29") (pin "1") (pinfunction "1_1") (pintype "passive"))
      (node (ref "R3") (pin "1") (pinfunction "1_1") (pintype "passive"))
      (node (ref "R30") (pin "2") (pinfunction "2_2") (pintype "passive"))
      (node (ref "R32") (pin "1") (pinfunction "1_1") (pintype "passive"))
      (node (ref "R34") (pin "1") (pinfunction "1_1") (pintype "passive"))
      (node (ref "R35") (pin "2") (pinfunction "2_2") (pintype "passive"))
      (node (ref "R37") (pin "1") (pinfunction "1_1") (pintype "passive"))
      (node (ref "R39") (pin "1") (pinfunction "1_1") (pintype "passive"))
      (node (ref "R40") (pin "2") (pinfunction "2_2") (pintype "passive"))
      (node (ref "R42") (pin "1") (pinfunction "1_1") (pintype "passive"))
      (node (ref "R44") (pin "1") (pinfunction "1_1") (pintype "passive"))
      (node (ref "R45") (pin "2") (pinfunction "2_2") (pintype "passive"))
      (node (ref "R47") (pin "1") (pinfunction "1_1") (pintype "passive"))
      (node (ref "R49") (pin "1") (pinfunction "1_1") (pintype "passive"))
      (node (ref "R50") (pin "2") (pinfunction "2_2") (pintype "passive"))
      (node (ref "R52") (pin "1") (pinfunction "1_1") (pintype "passive"))
      (node (ref "R54") (pin "1") (pinfunction "1_1") (pintype "passive"))
      (node (ref "R55") (pin "1") (pinfunction "1_1") (pintype "passive"))
      (node (ref "R56") (pin "1") (pinfunction "1_1") (pintype "passive"))
      (node (ref "R58") (pin "1") (pinfunction "1_1") (pintype "passive"))
      (node (ref "R59") (pin "1") (pinfunction "1_1") (pintype "passive"))
      (node (ref "R7") (pin "1") (pinfunction "1_1") (pintype "passive"))
      (node (ref "RANGE") (pin "3") (pinfunction "S_3") (pintype "passive"))
      (node (ref "RESET") (pin "GND") (pinfunction "GND_GND") (pintype "passive"))
      (node (ref "T1") (pin "E") (pinfunction "E_E") (pintype "bidirectional"))
      (node (ref "T2") (pin "E") (pinfunction "E_E") (pintype "bidirectional"))
      (node (ref "U1") (pin "21") (pinfunction "AGND_21") (pintype "bidirectional"))
      (node (ref "U1") (pin "3") (pinfunction "GND_3") (pintype "bidirectional"))
      (node (ref "U1") (pin "5") (pinfunction "GND_5") (pintype "bidirectional"))
      (node (ref "U4") (pin "6") (pinfunction "E_6") (pintype "bidirectional"))
      (node (ref "U4") (pin "7") (pinfunction "VEE_7") (pintype "bidirectional"))
      (node (ref "U4") (pin "8") (pinfunction "GND_8") (pintype "bidirectional"))
      (node (ref "U5") (pin "4") (pinfunction "GND_4") (pintype "input"))
    )
    (net (code "15") (name "MISO") (class "Default")
      (node (ref "ISP1") (pin "1") (pinfunction "MISO_1") (pintype "input"))
      (node (ref "U1") (pin "16") (pinfunction "PB4(MISO)_16") (pintype "bidirectional"))
      (node (ref "U4") (pin "10") (pinfunction "S1_10") (pintype "input"))
    )
    (net (code "16") (name "MOSI") (class "Default")
      (node (ref "ISP1") (pin "4") (pinfunction "MOSI_4") (pintype "output"))
      (node (ref "U1") (pin "15") (pinfunction "PB3(MOSI/OC2)_15") (pintype "bidirectional"))
      (node (ref "U4") (pin "11") (pinfunction "S0_11") (pintype "input"))
    )
    (net (code "17") (name "Net-(CLK_IN-PadNORM)") (class "Default")
      (node (ref "CLK_IN") (pin "NORM") (pinfunction "NORM_NORM") (pintype "passive"))
      (node (ref "R11") (pin "1") (pinfunction "1_1") (pintype "passive"))
      (node (ref "R13") (pin "1") (pinfunction "1_1") (pintype "passive"))
    )
    (net (code "18") (name "Net-(CLK_IN-PadTIP)") (class "Default")
      (node (ref "CLK_IN") (pin "TIP") (pinfunction "TIP_TIP") (pintype "passive"))
      (node (ref "R6") (pin "2") (pinfunction "2_2") (pintype "passive"))
      (node (ref "R61") (pin "1") (pinfunction "1_1") (pintype "passive"))
    )
    (net (code "19") (name "Net-(CLOCK_OUT-PadTIP)") (class "Default")
      (node (ref "CLOCK_OUT") (pin "TIP") (pinfunction "TIP_TIP") (pintype "passive"))
      (node (ref "R14") (pin "1") (pinfunction "1_1") (pintype "passive"))
    )
    (net (code "20") (name "Net-(CV_OUT-PadTIP)") (class "Default")
      (node (ref "CV_OUT") (pin "TIP") (pinfunction "TIP_TIP") (pintype "passive"))
      (node (ref "R2") (pin "2") (pinfunction "2_2") (pintype "passive"))
      (node (ref "R4") (pin "2") (pinfunction "2_2") (pintype "passive"))
    )
    (net (code "21") (name "Net-(D1-PadA)") (class "Default")
      (node (ref "D1") (pin "A") (pinfunction "A_A") (pintype "passive"))
      (node (ref "JP1") (pin "10") (pinfunction "10_10") (pintype "passive"))
      (node (ref "JP1") (pin "9") (pinfunction "9_9") (pintype "passive"))
    )
    (net (code "22") (name "Net-(D2-PadC)") (class "Default")
      (node (ref "D2") (pin "C") (pinfunction "C_C") (pintype "passive"))
      (node (ref "JP1") (pin "1") (pinfunction "1_1") (pintype "passive"))
      (node (ref "JP1") (pin "2") (pinfunction "2_2") (pintype "passive"))
    )
    (net (code "23") (name "Net-(D3-A)") (class "Default")
      (node (ref "D3") (pin "2") (pinfunction "A_2") (pintype "passive"))
      (node (ref "R16") (pin "2") (pinfunction "2_2") (pintype "passive"))
      (node (ref "R18") (pin "2") (pinfunction "2_2") (pintype "passive"))
    )
    (net (code "24") (name "Net-(D3-C)") (class "Default")
      (node (ref "D3") (pin "1") (pinfunction "C_1") (pintype "passive"))
      (node (ref "GATE1") (pin "TIP") (pinfunction "TIP_TIP") (pintype "passive"))
    )
    (net (code "25") (name "Net-(D4-A)") (class "Default")
      (node (ref "D4") (pin "2") (pinfunction "A_2") (pintype "passive"))
      (node (ref "R21") (pin "2") (pinfunction "2_2") (pintype "passive"))
      (node (ref "R23") (pin "2") (pinfunction "2_2") (pintype "passive"))
    )
    (net (code "26") (name "Net-(D4-C)") (class "Default")
      (node (ref "D4") (pin "1") (pinfunction "C_1") (pintype "passive"))
      (node (ref "GATE2") (pin "TIP") (pinfunction "TIP_TIP") (pintype "passive"))
    )
    (net (code "27") (name "Net-(D5-A)") (class "Default")
      (node (ref "D5") (pin "2") (pinfunction "A_2") (pintype "passive"))
      (node (ref "R26") (pin "2") (pinfunction "2_2") (pintype "passive"))
      (node (ref "R28") (pin "2") (pinfunction "2_2") (pintype "passive"))
    )
    (net (code "28") (name "Net-(D5-C)") (class "Default")
      (node (ref "D5") (pin "1") (pinfunction "C_1") (pintype "passive"))
      (node (ref "GATE3") (pin "TIP") (pinfunction "TIP_TIP") (pintype "passive"))
    )
    (net (code "29") (name "Net-(D6-A)") (class "Default")
      (node (ref "D6") (pin "2") (pinfunction "A_2") (pintype "passive"))
      (node (ref "R31") (pin "2") (pinfunction "2_2") (pintype "passive"))
      (node (ref "R33") (pin "2") (pinfunction "2_2") (pintype "passive"))
    )
    (net (code "30") (name "Net-(D6-C)") (class "Default")
      (node (ref "D6") (pin "1") (pinfunction "C_1") (pintype "passive"))
      (node (ref "GATE4") (pin "TIP") (pinfunction "TIP_TIP") (pintype "passive"))
    )
    (net (code "31") (name "Net-(D7-A)") (class "Default")
      (node (ref "D7") (pin "2") (pinfunction "A_2") (pintype "passive"))
      (node (ref "R36") (pin "2") (pinfunction "2_2") (pintype "passive"))
      (node (ref "R38") (pin "2") (pinfunction "2_2") (pintype "passive"))
    )
    (net (code "32") (name "Net-(D7-C)") (class "Default")
      (node (ref "D7") (pin "1") (pinfunction "C_1") (pintype "passive"))
      (node (ref "GATE5") (pin "TIP") (pinfunction "TIP_TIP") (pintype "passive"))
    )
    (net (code "33") (name "Net-(D8-A)") (class "Default")
      (node (ref "D8") (pin "2") (pinfunction "A_2") (pintype "passive"))
      (node (ref "R41") (pin "2") (pinfunction "2_2") (pintype "passive"))
      (node (ref "R43") (pin "2") (pinfunction "2_2") (pintype "passive"))
    )
    (net (code "34") (name "Net-(D8-C)") (class "Default")
      (node (ref "D8") (pin "1") (pinfunction "C_1") (pintype "passive"))
      (node (ref "GATE6") (pin "TIP") (pinfunction "TIP_TIP") (pintype "passive"))
    )
    (net (code "35") (name "Net-(D9-A)") (class "Default")
      (node (ref "D9") (pin "2") (pinfunction "A_2") (pintype "passive"))
      (node (ref "R46") (pin "2") (pinfunction "2_2") (pintype "passive"))
      (node (ref "R48") (pin "2") (pinfunction "2_2") (pintype "passive"))
    )
    (net (code "36") (name "Net-(D9-C)") (class "Default")
      (node (ref "D9") (pin "1") (pinfunction "C_1") (pintype "passive"))
      (node (ref "GATE7") (pin "TIP") (pinfunction "TIP_TIP") (pintype "passive"))
    )
    (net (code "37") (name "Net-(D10-A)") (class "Default")
      (node (ref "D10") (pin "2") (pinfunction "A_2") (pintype "passive"))
      (node (ref "R51") (pin "2") (pinfunction "2_2") (pintype "passive"))
      (node (ref "R53") (pin "2") (pinfunction "2_2") (pintype "passive"))
    )
    (net (code "38") (name "Net-(D10-C)") (class "Default")
      (node (ref "D10") (pin "1") (pinfunction "C_1") (pintype "passive"))
      (node (ref "GATE8") (pin "TIP") (pinfunction "TIP_TIP") (pintype "passive"))
    )
    (net (code "39") (name "Net-(DIRSW-O)") (class "Default")
      (node (ref "DIRSW") (pin "1") (pinfunction "O_1") (pintype "passive"))
      (node (ref "R58") (pin "2") (pinfunction "2_2") (pintype "passive"))
      (node (ref "U1") (pin "10") (pinfunction "PD6(AIN0)_10") (pintype "bidirectional"))
    )
    (net (code "40") (name "Net-(DIRSW-P)") (class "Default")
      (node (ref "DIRSW") (pin "2") (pinfunction "P_2") (pintype "passive"))
      (node (ref "R57") (pin "2") (pinfunction "2_2") (pintype "passive"))
    )
    (net (code "41") (name "Net-(DIRSW-S)") (class "Default")
      (node (ref "DIRSW") (pin "3") (pinfunction "S_3") (pintype "passive"))
      (node (ref "R59") (pin "2") (pinfunction "2_2") (pintype "passive"))
      (node (ref "U1") (pin "11") (pinfunction "PD7(AIN1)_11") (pintype "bidirectional"))
    )
    (net (code "42") (name "Net-(FADER1B-C)") (class "Default")
      (node (ref "FADER1") (pin "K") (pinfunction "C_K") (pintype "passive"))
      (node (ref "R15") (pin "1") (pinfunction "1_1") (pintype "passive"))
    )
    (net (code "43") (name "Net-(FADER2B-C)") (class "Default")
      (node (ref "FADER2") (pin "K") (pinfunction "C_K") (pintype "passive"))
      (node (ref "R20") (pin "1") (pinfunction "1_1") (pintype "passive"))
    )
    (net (code "44") (name "Net-(FADER3B-C)") (class "Default")
      (node (ref "FADER3") (pin "K") (pinfunction "C_K") (pintype "passive"))
      (node (ref "R25") (pin "1") (pinfunction "1_1") (pintype "passive"))
    )
    (net (code "45") (name "Net-(FADER4B-C)") (class "Default")
      (node (ref "FADER4") (pin "K") (pinfunction "C_K") (pintype "passive"))
      (node (ref "R30") (pin "1") (pinfunction "1_1") (pintype "passive"))
    )
    (net (code "46") (name "Net-(FADER5B-C)") (class "Default")
      (node (ref "FADER5") (pin "K") (pinfunction "C_K") (pintype "passive"))
      (node (ref "R35") (pin "1") (pinfunction "1_1") (pintype "passive"))
    )
    (net (code "47") (name "Net-(FADER6B-C)") (class "Default")
      (node (ref "FADER6") (pin "K") (pinfunction "C_K") (pintype "passive"))
      (node (ref "R40") (pin "1") (pinfunction "1_1") (pintype "passive"))
    )
    (net (code "48") (name "Net-(FADER7B-C)") (class "Default")
      (node (ref "FADER7") (pin "K") (pinfunction "C_K") (pintype "passive"))
      (node (ref "R45") (pin "1") (pinfunction "1_1") (pintype "passive"))
    )
    (net (code "49") (name "Net-(FADER8B-C)") (class "Default")
      (node (ref "FADER8") (pin "K") (pinfunction "C_K") (pintype "passive"))
      (node (ref "R50") (pin "1") (pinfunction "1_1") (pintype "passive"))
    )
    (net (code "50") (name "Net-(GLIDE-1)") (class "Default")
      (node (ref "GLIDE") (pin "P$1") (pinfunction "1_P$1") (pintype "passive"))
      (node (ref "R1") (pin "2") (pinfunction "2_2") (pintype "passive"))
    )
    (net (code "51") (name "Net-(GLIDE-2)") (class "Default")
      (node (ref "C3") (pin "1") (pinfunction "1_1") (pintype "passive"))
      (node (ref "GLIDE") (pin "P$2") (pinfunction "2_P$2") (pintype "passive"))
      (node (ref "GLIDE") (pin "P$3") (pinfunction "3_P$3") (pintype "passive"))
      (node (ref "U6") (pin "1+IN") (pinfunction "+IN_1+IN") (pintype "bidirectional"))
    )
    (net (code "52") (name "Net-(GLIDE1-2)") (class "Default")
      (node (ref "GLIDE1") (pin "P$2") (pinfunction "2_P$2") (pintype "passive"))
      (node (ref "U1") (pin "22") (pinfunction "ADC7_22") (pintype "bidirectional"))
    )
    (net (code "53") (name "Net-(R6-Pad1)") (class "Default")
      (node (ref "R6") (pin "1") (pinfunction "1_1") (pintype "passive"))
      (node (ref "R7") (pin "2") (pinfunction "2_2") (pintype "passive"))
      (node (ref "T1") (pin "B") (pinfunction "B_B") (pintype "bidirectional"))
    )
    (net (code "54") (name "Net-(R9-Pad2)") (class "Default")
      (node (ref "R9") (pin "2") (pinfunction "2_2") (pintype "passive"))
      (node (ref "RESET") (pin "TIP") (pinfunction "TIP_TIP") (pintype "passive"))
    )
    (net (code "55") (name "Net-(R10-Pad2)") (class "Default")
      (node (ref "R10") (pin "2") (pinfunction "2_2") (pintype "passive"))
      (node (ref "R9") (pin "1") (pinfunction "1_1") (pintype "passive"))
      (node (ref "T2") (pin "B") (pinfunction "B_B") (pintype "bidirectional"))
    )
    (net (code "56") (name "Net-(RANGE-P)") (class "Default")
      (node (ref "RANGE") (pin "2") (pinfunction "P_2") (pintype "passive"))
      (node (ref "TR1") (pin "2") (pinfunction "2_2") (pintype "passive"))
      (node (ref "TR1") (pin "3") (pinfunction "3_3") (pintype "passive"))
    )
    (net (code "57") (name "Net-(U$7A-1)") (class "Default")
      (node (ref "R55") (pin "2") (pinfunction "2_2") (pintype "passive"))
      (node (ref "U$7") (pin "1") (pinfunction "3_1") (pintype "bidirectional"))
      (node (ref "U$7") (pin "2") (pinfunction "1_2") (pintype "bidirectional"))
      (node (ref "U1") (pin "2") (pinfunction "PD4(XCK/T0)_2") (pintype "bidirectional"))
    )
    (net (code "58") (name "Net-(U$7B-C)") (class "Default")
      (node (ref "R56") (pin "2") (pinfunction "2_2") (pintype "passive"))
      (node (ref "U$7") (pin "K") (pinfunction "C_K") (pintype "passive"))
    )
    (net (code "59") (name "Net-(U1-PB6(XTAL1{slash}TOSC1))") (class "Default")
      (node (ref "C1") (pin "1") (pinfunction "1_1") (pintype "passive"))
      (node (ref "Q1") (pin "2") (pinfunction "2_2") (pintype "passive"))
      (node (ref "U1") (pin "7") (pinfunction "PB6(XTAL1/TOSC1)_7") (pintype "bidirectional"))
    )
    (net (code "60") (name "Net-(U1-PB7(XTAL2{slash}TOSC2))") (class "Default")
      (node (ref "C2") (pin "1") (pinfunction "1_1") (pintype "passive"))
      (node (ref "Q1") (pin "1") (pinfunction "1_1") (pintype "passive"))
      (node (ref "U1") (pin "8") (pinfunction "PB7(XTAL2/TOSC2)_8") (pintype "bidirectional"))
    )
    (net (code "61") (name "Net-(U1-PD5(T1))") (class "Default")
      (node (ref "U$7") (pin "A") (pinfunction "A_A") (pintype "passive"))
      (node (ref "U1") (pin "9") (pinfunction "PD5(T1)_9") (pintype "bidirectional"))
    )
    (net (code "62") (name "Net-(U2A--IN)") (class "Default")
      (node (ref "C10") (pin "1") (pinfunction "1_1") (pintype "passive"))
      (node (ref "R16") (pin "1") (pinfunction "1_1") (pintype "passive"))
      (node (ref "R17") (pin "2") (pinfunction "2_2") (pintype "passive"))
      (node (ref "U2") (pin "1-IN") (pinfunction "-IN_1-IN") (pintype "bidirectional"))
    )
    (net (code "63") (name "Net-(U2A-OUT)") (class "Default")
      (node (ref "C10") (pin "2") (pinfunction "2_2") (pintype "passive"))
      (node (ref "R18") (pin "1") (pinfunction "1_1") (pintype "passive"))
      (node (ref "U2") (pin "1OUT") (pinfunction "OUT_1OUT") (pintype "bidirectional"))
    )
    (net (code "64") (name "Net-(U2B--IN)") (class "Default")
      (node (ref "C12") (pin "1") (pinfunction "1_1") (pintype "passive"))
      (node (ref "R21") (pin "1") (pinfunction "1_1") (pintype "passive"))
      (node (ref "R22") (pin "2") (pinfunction "2_2") (pintype "passive"))
      (node (ref "U2") (pin "2-IN") (pinfunction "-IN_2-IN") (pintype "bidirectional"))
    )
    (net (code "65") (name "Net-(U2B-OUT)") (class "Default")
      (node (ref "C12") (pin "2") (pinfunction "2_2") (pintype "passive"))
      (node (ref "R23") (pin "1") (pinfunction "1_1") (pintype "passive"))
      (node (ref "U2") (pin "2OUT") (pinfunction "OUT_2OUT") (pintype "bidirectional"))
    )
    (net (code "66") (name "Net-(U2C--IN)") (class "Default")
      (node (ref "C14") (pin "1") (pinfunction "1_1") (pintype "passive"))
      (node (ref "R26") (pin "1") (pinfunction "1_1") (pintype "passive"))
      (node (ref "R27") (pin "2") (pinfunction "2_2") (pintype "passive"))
      (node (ref "U2") (pin "3-IN") (pinfunction "-IN_3-IN") (pintype "bidirectional"))
    )
    (net (code "67") (name "Net-(U2C-OUT)") (class "Default")
      (node (ref "C14") (pin "2") (pinfunction "2_2") (pintype "passive"))
      (node (ref "R28") (pin "1") (pinfunction "1_1") (pintype "passive"))
      (node (ref "U2") (pin "3OUT") (pinfunction "OUT_3OUT") (pintype "bidirectional"))
    )
    (net (code "68") (name "Net-(U2D--IN)") (class "Default")
      (node (ref "C16") (pin "1") (pinfunction "1_1") (pintype "passive"))
      (node (ref "R31") (pin "1") (pinfunction "1_1") (pintype "passive"))
      (node (ref "R32") (pin "2") (pinfunction "2_2") (pintype "passive"))
      (node (ref "U2") (pin "4-IN") (pinfunction "-IN_4-IN") (pintype "bidirectional"))
    )
    (net (code "69") (name "Net-(U2D-OUT)") (class "Default")
      (node (ref "C16") (pin "2") (pinfunction "2_2") (pintype "passive"))
      (node (ref "R33") (pin "1") (pinfunction "1_1") (pintype "passive"))
      (node (ref "U2") (pin "4OUT") (pinfunction "OUT_4OUT") (pintype "bidirectional"))
    )
    (net (code "70") (name "Net-(U3A--IN)") (class "Default")
      (node (ref "C18") (pin "1") (pinfunction "1_1") (pintype "passive"))
      (node (ref "R36") (pin "1") (pinfunction "1_1") (pintype "passive"))
      (node (ref "R37") (pin "2") (pinfunction "2_2") (pintype "passive"))
      (node (ref "U3") (pin "1-IN") (pinfunction "-IN_1-IN") (pintype "bidirectional"))
    )
    (net (code "71") (name "Net-(U3A-OUT)") (class "Default")
      (node (ref "C18") (pin "2") (pinfunction "2_2") (pintype "passive"))
      (node (ref "R38") (pin "1") (pinfunction "1_1") (pintype "passive"))
      (node (ref "U3") (pin "1OUT") (pinfunction "OUT_1OUT") (pintype "bidirectional"))
    )
    (net (code "72") (name "Net-(U3B--IN)") (class "Default")
      (node (ref "C20") (pin "1") (pinfunction "1_1") (pintype "passive"))
      (node (ref "R41") (pin "1") (pinfunction "1_1") (pintype "passive"))
      (node (ref "R42") (pin "2") (pinfunction "2_2") (pintype "passive"))
      (node (ref "U3") (pin "2-IN") (pinfunction "-IN_2-IN") (pintype "bidirectional"))
    )
    (net (code "73") (name "Net-(U3B-OUT)") (class "Default")
      (node (ref "C20") (pin "2") (pinfunction "2_2") (pintype "passive"))
      (node (ref "R43") (pin "1") (pinfunction "1_1") (pintype "passive"))
      (node (ref "U3") (pin "2OUT") (pinfunction "OUT_2OUT") (pintype "bidirectional"))
    )
    (net (code "74") (name "Net-(U3C--IN)") (class "Default")
      (node (ref "C22") (pin "1") (pinfunction "1_1") (pintype "passive"))
      (node (ref "R46") (pin "1") (pinfunction "1_1") (pintype "passive"))
      (node (ref "R47") (pin "2") (pinfunction "2_2") (pintype "passive"))
      (node (ref "U3") (pin "3-IN") (pinfunction "-IN_3-IN") (pintype "bidirectional"))
    )
    (net (code "75") (name "Net-(U3C-OUT)") (class "Default")
      (node (ref "C22") (pin "2") (pinfunction "2_2") (pintype "passive"))
      (node (ref "R48") (pin "1") (pinfunction "1_1") (pintype "passive"))
      (node (ref "U3") (pin "3OUT") (pinfunction "OUT_3OUT") (pintype "bidirectional"))
    )
    (net (code "76") (name "Net-(U3D--IN)") (class "Default")
      (node (ref "C24") (pin "1") (pinfunction "1_1") (pintype "passive"))
      (node (ref "R51") (pin "1") (pinfunction "1_1") (pintype "passive"))
      (node (ref "R52") (pin "2") (pinfunction "2_2") (pintype "passive"))
      (node (ref "U3") (pin "4-IN") (pinfunction "-IN_4-IN") (pintype "bidirectional"))
    )
    (net (code "77") (name "Net-(U3D-OUT)") (class "Default")
      (node (ref "C24") (pin "2") (pinfunction "2_2") (pintype "passive"))
      (node (ref "R53") (pin "1") (pinfunction "1_1") (pintype "passive"))
      (node (ref "U3") (pin "4OUT") (pinfunction "OUT_4OUT") (pintype "bidirectional"))
    )
    (net (code "78") (name "Net-(U4-Y0)") (class "Default")
      (node (ref "FADER1") (pin "2") (pinfunction "2_2") (pintype "passive"))
      (node (ref "U4") (pin "13") (pinfunction "Y0_13") (pintype "bidirectional"))
    )
    (net (code "79") (name "Net-(U4-Y1)") (class "Default")
      (node (ref "FADER2") (pin "2") (pinfunction "2_2") (pintype "passive"))
      (node (ref "U4") (pin "14") (pinfunction "Y1_14") (pintype "bidirectional"))
    )
    (net (code "80") (name "Net-(U4-Y2)") (class "Default")
      (node (ref "FADER3") (pin "2") (pinfunction "2_2") (pintype "passive"))
      (node (ref "U4") (pin "15") (pinfunction "Y2_15") (pintype "bidirectional"))
    )
    (net (code "81") (name "Net-(U4-Y3)") (class "Default")
      (node (ref "FADER4") (pin "2") (pinfunction "2_2") (pintype "passive"))
      (node (ref "U4") (pin "12") (pinfunction "Y3_12") (pintype "bidirectional"))
    )
    (net (code "82") (name "Net-(U4-Y4)") (class "Default")
      (node (ref "FADER5") (pin "2") (pinfunction "2_2") (pintype "passive"))
      (node (ref "U4") (pin "1") (pinfunction "Y4_1") (pintype "bidirectional"))
    )
    (net (code "83") (name "Net-(U4-Y5)") (class "Default")
      (node (ref "FADER6") (pin "2") (pinfunction "2_2") (pintype "passive"))
      (node (ref "U4") (pin "5") (pinfunction "Y5_5") (pintype "bidirectional"))
    )
    (net (code "84") (name "Net-(U4-Y6)") (class "Default")
      (node (ref "FADER7") (pin "2") (pinfunction "2_2") (pintype "passive"))
      (node (ref "U4") (pin "2") (pinfunction "Y6_2") (pintype "bidirectional"))
    )
    (net (code "85") (name "Net-(U4-Y7)") (class "Default")
      (node (ref "FADER8") (pin "2") (pinfunction "2_2") (pintype "passive"))
      (node (ref "U4") (pin "4") (pinfunction "Y7_4") (pintype "bidirectional"))
    )
    (net (code "86") (name "Net-(U4-Z)") (class "Default")
      (node (ref "R60") (pin "2") (pinfunction "2_2") (pintype "passive"))
      (node (ref "U4") (pin "3") (pinfunction "Z_3") (pintype "bidirectional"))
    )
    (net (code "87") (name "Net-(U6A--IN)") (class "Default")
      (node (ref "C6") (pin "1") (pinfunction "1_1") (pintype "passive"))
      (node (ref "R2") (pin "1") (pinfunction "1_1") (pintype "passive"))
      (node (ref "R3") (pin "2") (pinfunction "2_2") (pintype "passive"))
      (node (ref "U6") (pin "1-IN") (pinfunction "-IN_1-IN") (pintype "bidirectional"))
    )
    (net (code "88") (name "Net-(U6A-OUT)") (class "Default")
      (node (ref "C6") (pin "2") (pinfunction "2_2") (pintype "passive"))
      (node (ref "R4") (pin "1") (pinfunction "1_1") (pintype "passive"))
      (node (ref "U6") (pin "1OUT") (pinfunction "OUT_1OUT") (pintype "bidirectional"))
    )
    (net (code "89") (name "Net-(U6B-+IN)") (class "Default")
      (node (ref "R61") (pin "2") (pinfunction "2_2") (pintype "passive"))
      (node (ref "U6") (pin "2+IN") (pinfunction "+IN_2+IN") (pintype "bidirectional"))
    )
    (net (code "90") (name "Net-(U6B--IN)") (class "Default")
      (node (ref "R14") (pin "2") (pinfunction "2_2") (pintype "passive"))
      (node (ref "U6") (pin "2-IN") (pinfunction "-IN_2-IN") (pintype "bidirectional"))
      (node (ref "U6") (pin "2OUT") (pinfunction "OUT_2OUT") (pintype "bidirectional"))
    )
    (net (code "91") (name "Net-(U6C--IN)") (class "Default")
      (node (ref "C7") (pin "1") (pinfunction "1_1") (pintype "passive"))
      (node (ref "R11") (pin "2") (pinfunction "2_2") (pintype "passive"))
      (node (ref "R12") (pin "1") (pinfunction "1_1") (pintype "passive"))
      (node (ref "U6") (pin "3-IN") (pinfunction "-IN_3-IN") (pintype "bidirectional"))
    )
    (net (code "92") (name "Net-(U6C-OUT)") (class "Default")
      (node (ref "C7") (pin "2") (pinfunction "2_2") (pintype "passive"))
      (node (ref "R13") (pin "2") (pinfunction "2_2") (pintype "passive"))
      (node (ref "U6") (pin "3OUT") (pinfunction "OUT_3OUT") (pintype "bidirectional"))
    )
    (net (code "93") (name "Net-(U6D-+IN)") (class "Default")
      (node (ref "R60") (pin "1") (pinfunction "1_1") (pintype "passive"))
      (node (ref "TR1") (pin "1") (pinfunction "1_1") (pintype "passive"))
      (node (ref "U6") (pin "4+IN") (pinfunction "+IN_4+IN") (pintype "bidirectional"))
    )
    (net (code "94") (name "Net-(U6D--IN)") (class "Default")
      (node (ref "R1") (pin "1") (pinfunction "1_1") (pintype "passive"))
      (node (ref "U6") (pin "4-IN") (pinfunction "-IN_4-IN") (pintype "bidirectional"))
      (node (ref "U6") (pin "4OUT") (pinfunction "OUT_4OUT") (pintype "bidirectional"))
    )
    (net (code "95") (name "RESET") (class "Default")
      (node (ref "R8") (pin "1") (pinfunction "1_1") (pintype "passive"))
      (node (ref "T2") (pin "C") (pinfunction "C_C") (pintype "bidirectional"))
      (node (ref "U1") (pin "1") (pinfunction "PD3(INT1)_1") (pintype "bidirectional"))
    )
    (net (code "96") (name "RST") (class "Default")
      (node (ref "ISP1") (pin "5") (pinfunction "RST_5") (pintype "output"))
      (node (ref "U1") (pin "29") (pinfunction "PC6(/RESET)_29") (pintype "bidirectional"))
    )
    (net (code "97") (name "SCK") (class "Default")
      (node (ref "ISP1") (pin "3") (pinfunction "SCK_3") (pintype "output"))
      (node (ref "U1") (pin "17") (pinfunction "PB5(SCK)_17") (pintype "bidirectional"))
      (node (ref "U4") (pin "9") (pinfunction "S2_9") (pintype "input"))
    )
    (net (code "98") (name "unconnected-(CLOCK_OUT-PadNORM)") (class "Default")
      (node (ref "CLOCK_OUT") (pin "NORM") (pinfunction "NORM_NORM") (pintype "passive"))
    )
    (net (code "99") (name "unconnected-(CV_OUT-PadNORM)") (class "Default")
      (node (ref "CV_OUT") (pin "NORM") (pinfunction "NORM_NORM") (pintype "passive"))
    )
    (net (code "100") (name "unconnected-(GATE1-PadNORM)") (class "Default")
      (node (ref "GATE1") (pin "NORM") (pinfunction "NORM_NORM") (pintype "passive"))
    )
    (net (code "101") (name "unconnected-(GATE2-PadNORM)") (class "Default")
      (node (ref "GATE2") (pin "NORM") (pinfunction "NORM_NORM") (pintype "passive"))
    )
    (net (code "102") (name "unconnected-(GATE3-PadNORM)") (class "Default")
      (node (ref "GATE3") (pin "NORM") (pinfunction "NORM_NORM") (pintype "passive"))
    )
    (net (code "103") (name "unconnected-(GATE4-PadNORM)") (class "Default")
      (node (ref "GATE4") (pin "NORM") (pinfunction "NORM_NORM") (pintype "passive"))
    )
    (net (code "104") (name "unconnected-(GATE5-PadNORM)") (class "Default")
      (node (ref "GATE5") (pin "NORM") (pinfunction "NORM_NORM") (pintype "passive"))
    )
    (net (code "105") (name "unconnected-(GATE6-PadNORM)") (class "Default")
      (node (ref "GATE6") (pin "NORM") (pinfunction "NORM_NORM") (pintype "passive"))
    )
    (net (code "106") (name "unconnected-(GATE7-PadNORM)") (class "Default")
      (node (ref "GATE7") (pin "NORM") (pinfunction "NORM_NORM") (pintype "passive"))
    )
    (net (code "107") (name "unconnected-(GATE8-PadNORM)") (class "Default")
      (node (ref "GATE8") (pin "NORM") (pinfunction "NORM_NORM") (pintype "passive"))
    )
    (net (code "108") (name "unconnected-(RANGE-O-Pad1)") (class "Default")
      (node (ref "RANGE") (pin "1") (pinfunction "O_1") (pintype "passive"))
    )
    (net (code "109") (name "unconnected-(RESET-PadNORM)") (class "Default")
      (node (ref "RESET") (pin "NORM") (pinfunction "NORM_NORM") (pintype "passive"))
    )
    (net (code "110") (name "unconnected-(U1-ADC6-Pad19)") (class "Default")
      (node (ref "U1") (pin "19") (pinfunction "ADC6_19") (pintype "bidirectional"))
    )
    (net (code "111") (name "unconnected-(U1-AREF-Pad20)") (class "Default")
      (node (ref "U1") (pin "20") (pinfunction "AREF_20") (pintype "bidirectional"))
    )
    (net (code "112") (name "unconnected-(U1-PD0(RXD)-Pad30)") (class "Default")
      (node (ref "U1") (pin "30") (pinfunction "PD0(RXD)_30") (pintype "bidirectional"))
    )
    (net (code "113") (name "unconnected-(U1-PD1(TXD)-Pad31)") (class "Default")
      (node (ref "U1") (pin "31") (pinfunction "PD1(TXD)_31") (pintype "bidirectional"))
    )
  )
)
